# IOandSensors.net
KiCad netlist of a schematic drawn in Altium Designer
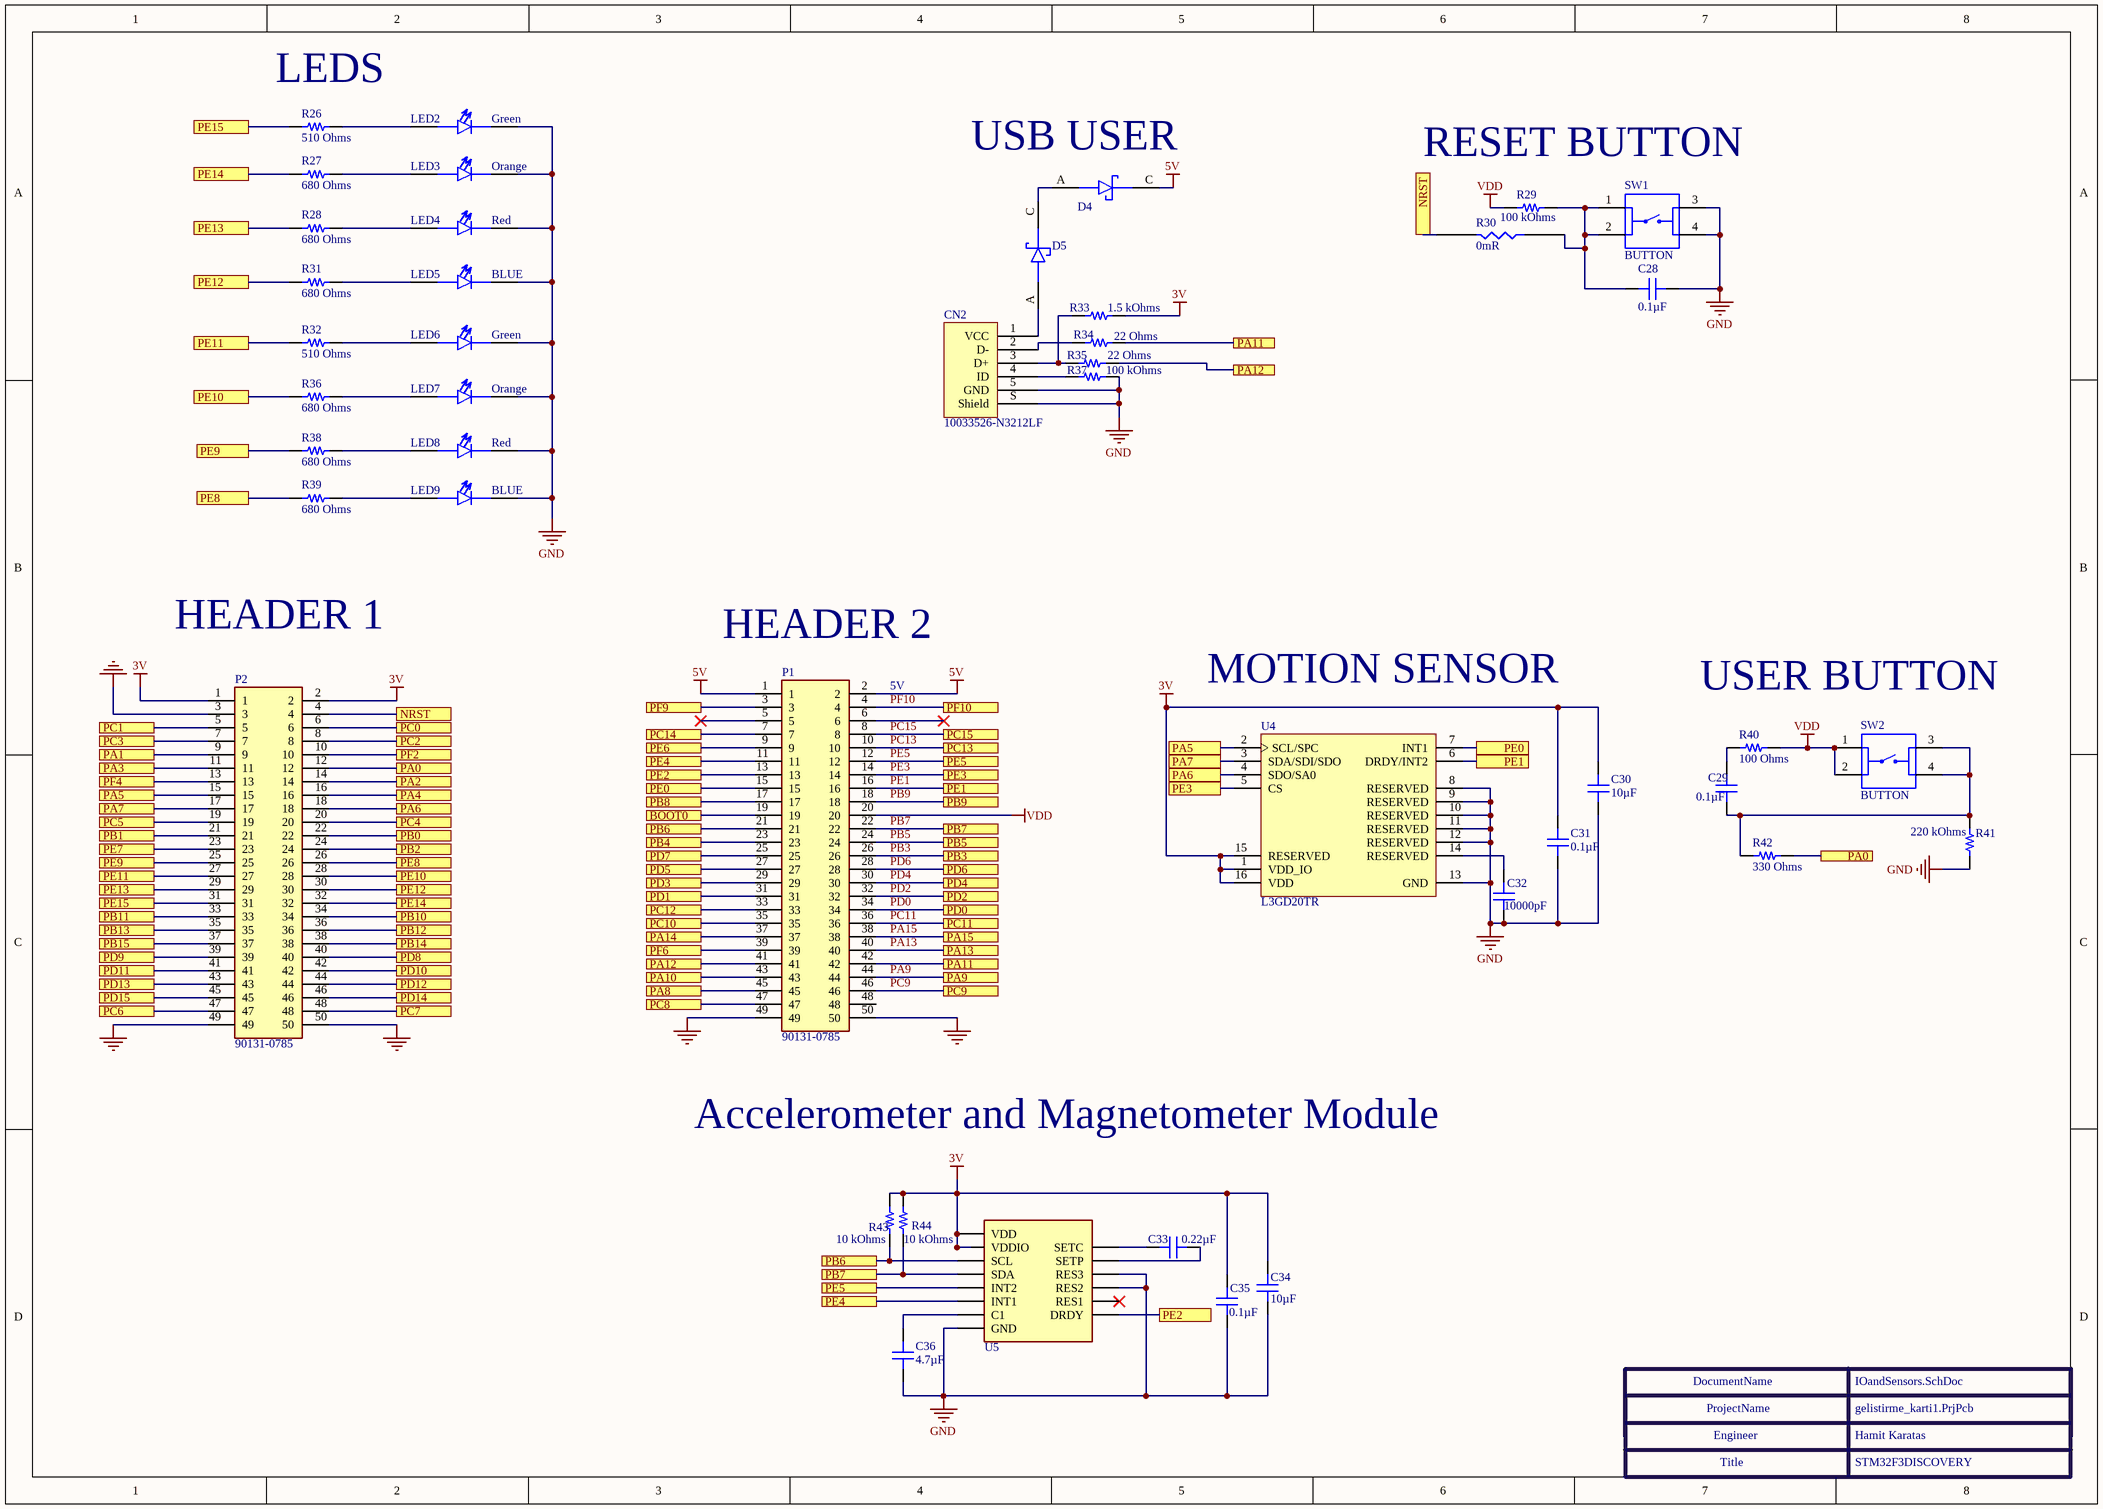
[diagram p0: IOandSensors.SchDoc]

(export (version "E")
  (design (tool "Eeschema 10.0.6"))
  (components
    (comp (ref "C28")
      (value "0.1µF")
      (footprint "CAP 0603_1608")
      (description "CAP CER 0.1UF 50V X7R 0603")
      (fields (field (name "PART NUMBER") "C0603C104K5RAC7411") (field (name "MANUFACTURER") "KEMET"))
      (libsource (lib "Celestial Altium Library - altium_library (4)") (part "Capacitor"))
    )
    (comp (ref "C29")
      (value "0.1µF")
      (footprint "CAP 0603_1608")
      (description "CAP CER 0.1UF 50V X7R 0603")
      (fields (field (name "PART NUMBER") "C0603C104K5RAC7411") (field (name "MANUFACTURER") "KEMET"))
      (libsource (lib "Celestial Altium Library - altium_library (4)") (part "Capacitor"))
    )
    (comp (ref "C30")
      (value "10µF")
      (footprint "CAP 0603_1608")
      (description "CAP CER 10UF 6.3V X5R 0603")
      (fields
        (field (name "PART NUMBER") "GRM188R60J106ME47D")
        (field (name "MANUFACTURER") "Murata Electronics")
      )
      (libsource (lib "Celestial Altium Library - altium_library (4)") (part "Capacitor"))
    )
    (comp (ref "C31")
      (value "0.1µF")
      (footprint "CAP 0603_1608")
      (description "CAP CER 0.1UF 50V X7R 0603")
      (fields (field (name "PART NUMBER") "C0603C104K5RAC7411") (field (name "MANUFACTURER") "KEMET"))
      (libsource (lib "Celestial Altium Library - altium_library (4)") (part "Capacitor"))
    )
    (comp (ref "C32")
      (value "10000pF")
      (footprint "CAP 0603_1608")
      (description "CAP CER 0603 10NF 100V X7R")
      (fields (field (name "PART NUMBER") "C0603X103K1RAC3316") (field (name "MANUFACTURER") "KEMET"))
      (libsource (lib "Celestial Altium Library - altium_library (4)") (part "Capacitor"))
    )
    (comp (ref "C33")
      (value "0.22µF")
      (footprint "CAP 0603_1608")
      (description "CAP CER 0603 220NF 16V X7R 10%")
      (fields (field (name "PART NUMBER") "C0603C224K4RECAUTO") (field (name "MANUFACTURER") "KEMET"))
      (libsource (lib "Celestial Altium Library - altium_library (4)") (part "Capacitor"))
    )
    (comp (ref "C34")
      (value "10µF")
      (footprint "CAP 0603_1608")
      (description "CAP CER 10UF 6.3V X5R 0603")
      (fields
        (field (name "PART NUMBER") "GRM188R60J106ME47D")
        (field (name "MANUFACTURER") "Murata Electronics")
      )
      (libsource (lib "Celestial Altium Library - altium_library (4)") (part "Capacitor"))
    )
    (comp (ref "C35")
      (value "0.1µF")
      (footprint "CAP 0603_1608")
      (description "CAP CER 0.1UF 50V X7R 0603")
      (fields (field (name "PART NUMBER") "C0603C104K5RAC7411") (field (name "MANUFACTURER") "KEMET"))
      (libsource (lib "Celestial Altium Library - altium_library (4)") (part "Capacitor"))
    )
    (comp (ref "C36")
      (value "4.7µF")
      (footprint "CAP 0603_1608")
      (description "CAP CER 4.7UF 6.3V X5R 0603")
      (fields (field (name "PART NUMBER") "C0603C475K9PACTU") (field (name "MANUFACTURER") "KEMET"))
      (libsource (lib "Celestial Altium Library - altium_library (4)") (part "Capacitor"))
    )
    (comp (ref "CN2")
      (value "10033526-N3212LF")
      (footprint "FCI USB 10033526-N3212LF")
      (description "CONN RCPT MINI USB B 5POS SMD RA")
      (fields (field (name "MANUFACTURER") "Amphenol ICC (FCI)"))
      (libsource (lib "Celestial Altium Library - altium_library (4)") (part "USB 2.0 Type B Micro"))
    )
    (comp (ref "D4")
      (value "BAT60J")
      (footprint "SOD-323")
      (fields
        (field (name "MANUFACTURER") "STMicroelectronics")
        (field (name "MANUFACTURER PART NUMBER") "BAT60JFILM")
      )
      (libsource (lib "giris_intlib") (part "DIODE SCHOTTKY"))
    )
    (comp (ref "D5")
      (value "BAT60J")
      (footprint "SOD-323")
      (fields
        (field (name "MANUFACTURER") "STMicroelectronics")
        (field (name "MANUFACTURER PART NUMBER") "BAT60JFILM")
      )
      (libsource (lib "giris_intlib") (part "DIODE SCHOTTKY"))
    )
    (comp (ref "LED2")
      (value "Green")
      (footprint "LED GREEN 0805")
      (description "Green 0805 130 º Min 5 mcd Typical 12 mcd Water Clear Lens SMT LED LTST-C171GKT")
      (fields
        (field (name "MANUFACTURER") "Vishay Lite-On")
        (field (name "MANUFACTURER PART NUMBER") "LTST-C171GKT")
        (field (name "DESIGNED BY") "Hamit")
      )
      (libsource (lib "giris_intlib") (part "LED GREEN 0805"))
    )
    (comp (ref "LED3")
      (value "Orange")
      (footprint "LED ORANGE 0805")
      (description "LED Uni-Color Orange 610nm 2-Pin Chip 0805(2012Metric) T/R  LO R976-PS-1")
      (fields
        (field (name "MANUFACTURER") "Osram Opto")
        (field (name "MANUFACTURER PART NUMBER") "LOR976-PS-1")
      )
      (libsource (lib "giris_intlib") (part "LED ORANGE 0805"))
    )
    (comp (ref "LED4")
      (value "Red")
      (footprint "LED RED 0805")
      (description "Single Color LED, Hyper Red, Colorless Diffused, 1.3mm LH R974-LP-1")
      (fields
        (field (name "MANUFACTURER") "Osram Opto")
        (field (name "MANUFACTURER PART NUMBER") "LH R974-LP-1")
        (field (name "DESIGNED BY") "Hamit")
      )
      (libsource (lib "giris_intlib") (part "LED RED 0805"))
    )
    (comp (ref "LED5")
      (value "BLUE")
      (footprint "LED BLUE 0805")
      (description "Standard LEDs - SMD BLUE 469nm 55mcd DIFF CMDA5CB7D1S")
      (fields
        (field (name "MANUFACTURER") "VCC CHML")
        (field (name "MANUFACTURER PART NUMBER") "CMDA5CB7D1S")
      )
      (libsource (lib "giris_intlib") (part "LED BLUE 0805"))
    )
    (comp (ref "LED6")
      (value "Green")
      (footprint "LED GREEN 0805")
      (description "Green 0805 130 º Min 5 mcd Typical 12 mcd Water Clear Lens SMT LED LTST-C171GKT")
      (fields
        (field (name "MANUFACTURER") "Vishay Lite-On")
        (field (name "MANUFACTURER PART NUMBER") "LTST-C171GKT")
        (field (name "DESIGNED BY") "Hamit")
      )
      (libsource (lib "giris_intlib") (part "LED GREEN 0805"))
    )
    (comp (ref "LED7")
      (value "Orange")
      (footprint "LED ORANGE 0805")
      (description "LED Uni-Color Orange 610nm 2-Pin Chip 0805(2012Metric) T/R  LO R976-PS-1")
      (fields
        (field (name "MANUFACTURER") "Osram Opto")
        (field (name "MANUFACTURER PART NUMBER") "LOR976-PS-1")
      )
      (libsource (lib "giris_intlib") (part "LED ORANGE 0805"))
    )
    (comp (ref "LED8")
      (value "Red")
      (footprint "LED RED 0805")
      (description "Single Color LED, Hyper Red, Colorless Diffused, 1.3mm LH R974-LP-1")
      (fields
        (field (name "MANUFACTURER") "Osram Opto")
        (field (name "MANUFACTURER PART NUMBER") "LH R974-LP-1")
        (field (name "DESIGNED BY") "Hamit")
      )
      (libsource (lib "giris_intlib") (part "LED RED 0805"))
    )
    (comp (ref "LED9")
      (value "BLUE")
      (footprint "LED BLUE 0805")
      (description "Standard LEDs - SMD BLUE 469nm 55mcd DIFF CMDA5CB7D1S")
      (fields
        (field (name "MANUFACTURER") "VCC CHML")
        (field (name "MANUFACTURER PART NUMBER") "CMDA5CB7D1S")
      )
      (libsource (lib "giris_intlib") (part "LED BLUE 0805"))
    )
    (comp (ref "P1")
      (value "90131-0785")
      (footprint "altium_giris:HDRV50W100P259X254_2X25_6350X516X595P")
      (description "Connector")
      (fields (field (name "MOUSER PART NUMBER") "538-90131-0785"))
      (libsource (lib "*") (part "90131-0785"))
    )
    (comp (ref "P2")
      (value "90131-0785")
      (footprint "altium_giris:HDRV50W100P259X254_2X25_6350X516X595P")
      (description "Connector")
      (fields (field (name "MOUSER PART NUMBER") "538-90131-0785"))
      (libsource (lib "*") (part "90131-0785"))
    )
    (comp (ref "R26")
      (value "510 Ohms")
      (footprint "RES 0603_1608")
      (description "RES SMD 510 OHM 0.5% 1/5W 0603")
      (fields
        (field (name "PART NUMBER") "ERJ-PB3D5100V")
        (field (name "MANUFACTURER") "Panasonic Electronic Components")
      )
      (libsource (lib "Celestial Altium Library - altium_library (4)") (part "Resistor"))
    )
    (comp (ref "R27")
      (value "680 Ohms")
      (footprint "RES 0603_1608")
      (description "RES 680 OHM 1% 1/8W 0603")
      (fields
        (field (name "PART NUMBER") "RK73H1JTTD6800F")
        (field (name "MANUFACTURER") "KOA Speer Electronics, Inc.")
      )
      (libsource (lib "Celestial Altium Library - altium_library (4)") (part "Resistor"))
    )
    (comp (ref "R28")
      (value "680 Ohms")
      (footprint "RES 0603_1608")
      (description "RES 680 OHM 1% 1/8W 0603")
      (fields
        (field (name "PART NUMBER") "RK73H1JTTD6800F")
        (field (name "MANUFACTURER") "KOA Speer Electronics, Inc.")
      )
      (libsource (lib "Celestial Altium Library - altium_library (4)") (part "Resistor"))
    )
    (comp (ref "R29")
      (value "100 kOhms")
      (footprint "RES 0603_1608")
      (description "RES SMD 100K OHM 0.5% 1/10W 0603")
      (fields (field (name "PART NUMBER") "AT0603DRD07100KL") (field (name "MANUFACTURER") "Yageo"))
      (libsource (lib "Celestial Altium Library - altium_library (4)") (part "Resistor"))
    )
    (comp (ref "R30")
      (value "RC0603JR-070RL")
      (footprint "RES_0603")
      (description "RES SMD 0 OHM JUMPER 1/10W 0603")
      (fields
        (field (name "MANUFACTURER") "Yageo")
        (field (name "TOLERANCE") "1%")
        (field (name "RESISTANCE") "0mR")
        (field (name "DESIGNED BY") "Hamit")
      )
      (libsource (lib "giris_intlib") (part "Res 0 ohm 0603"))
    )
    (comp (ref "R31")
      (value "680 Ohms")
      (footprint "RES 0603_1608")
      (description "RES 680 OHM 1% 1/8W 0603")
      (fields
        (field (name "PART NUMBER") "RK73H1JTTD6800F")
        (field (name "MANUFACTURER") "KOA Speer Electronics, Inc.")
      )
      (libsource (lib "Celestial Altium Library - altium_library (4)") (part "Resistor"))
    )
    (comp (ref "R32")
      (value "510 Ohms")
      (footprint "RES 0603_1608")
      (description "RES SMD 510 OHM 0.5% 1/5W 0603")
      (fields
        (field (name "PART NUMBER") "ERJ-PB3D5100V")
        (field (name "MANUFACTURER") "Panasonic Electronic Components")
      )
      (libsource (lib "Celestial Altium Library - altium_library (4)") (part "Resistor"))
    )
    (comp (ref "R33")
      (value "1.5 kOhms")
      (footprint "RES 0603_1608")
      (description "RES SMD 1.5K OHM 0.1% 1/10W 0603")
      (fields
        (field (name "PART NUMBER") "ERA-3AEB152V")
        (field (name "MANUFACTURER") "Panasonic Electronic Components")
      )
      (libsource (lib "Celestial Altium Library - altium_library (4)") (part "Resistor"))
    )
    (comp (ref "R34")
      (value "22 Ohms")
      (footprint "RES 0603_1608")
      (description "RES 22 OHM 5% 1/8W 0603")
      (fields
        (field (name "PART NUMBER") "RK73B1JTTD220J")
        (field (name "MANUFACTURER") "KOA Speer Electronics, Inc.")
      )
      (libsource (lib "Celestial Altium Library - altium_library (4)") (part "Resistor"))
    )
    (comp (ref "R35")
      (value "22 Ohms")
      (footprint "RES 0603_1608")
      (description "RES 22 OHM 5% 1/8W 0603")
      (fields
        (field (name "PART NUMBER") "RK73B1JTTD220J")
        (field (name "MANUFACTURER") "KOA Speer Electronics, Inc.")
      )
      (libsource (lib "Celestial Altium Library - altium_library (4)") (part "Resistor"))
    )
    (comp (ref "R36")
      (value "680 Ohms")
      (footprint "RES 0603_1608")
      (description "RES 680 OHM 1% 1/8W 0603")
      (fields
        (field (name "PART NUMBER") "RK73H1JTTD6800F")
        (field (name "MANUFACTURER") "KOA Speer Electronics, Inc.")
      )
      (libsource (lib "Celestial Altium Library - altium_library (4)") (part "Resistor"))
    )
    (comp (ref "R37")
      (value "100 kOhms")
      (footprint "RES 0603_1608")
      (description "RES SMD 100K OHM 0.5% 1/10W 0603")
      (fields (field (name "PART NUMBER") "AT0603DRD07100KL") (field (name "MANUFACTURER") "Yageo"))
      (libsource (lib "Celestial Altium Library - altium_library (4)") (part "Resistor"))
    )
    (comp (ref "R38")
      (value "680 Ohms")
      (footprint "RES 0603_1608")
      (description "RES 680 OHM 1% 1/8W 0603")
      (fields
        (field (name "PART NUMBER") "RK73H1JTTD6800F")
        (field (name "MANUFACTURER") "KOA Speer Electronics, Inc.")
      )
      (libsource (lib "Celestial Altium Library - altium_library (4)") (part "Resistor"))
    )
    (comp (ref "R39")
      (value "680 Ohms")
      (footprint "RES 0603_1608")
      (description "RES 680 OHM 1% 1/8W 0603")
      (fields
        (field (name "PART NUMBER") "RK73H1JTTD6800F")
        (field (name "MANUFACTURER") "KOA Speer Electronics, Inc.")
      )
      (libsource (lib "Celestial Altium Library - altium_library (4)") (part "Resistor"))
    )
    (comp (ref "R40")
      (value "100 Ohms")
      (footprint "RES 0603_1608")
      (description "RES 100 OHM 0.1% 1/16W 0603")
      (fields
        (field (name "PART NUMBER") "RNCS0603BKE100R")
        (field (name "MANUFACTURER") "Stackpole Electronics Inc")
      )
      (libsource (lib "Celestial Altium Library - altium_library (4)") (part "Resistor"))
    )
    (comp (ref "R41")
      (value "220 kOhms")
      (footprint "RES 0603_1608")
      (description "RES SMD 220K OHM 5% 1/10W 0603")
      (fields (field (name "PART NUMBER") "AC0603JR-07220KL") (field (name "MANUFACTURER") "Yageo"))
      (libsource (lib "Celestial Altium Library - altium_library (4)") (part "Resistor"))
    )
    (comp (ref "R42")
      (value "330 Ohms")
      (footprint "RES 0603_1608")
      (description "RES SMD 330 OHM 1% 1/10W 0603")
      (fields (field (name "PART NUMBER") "AF0603FR-07330RL") (field (name "MANUFACTURER") "Yageo"))
      (libsource (lib "Celestial Altium Library - altium_library (4)") (part "Resistor"))
    )
    (comp (ref "R43")
      (value "10 kOhms")
      (footprint "RES 0603_1608")
      (description "RES SMD 10K OHM 0.5% 1/10W 0603")
      (fields (field (name "PART NUMBER") "RT0603DRD0710KL") (field (name "MANUFACTURER") "Yageo"))
      (libsource (lib "Celestial Altium Library - altium_library (4)") (part "Resistor"))
    )
    (comp (ref "R44")
      (value "10 kOhms")
      (footprint "RES 0603_1608")
      (description "RES SMD 10K OHM 0.5% 1/10W 0603")
      (fields (field (name "PART NUMBER") "RT0603DRD0710KL") (field (name "MANUFACTURER") "Yageo"))
      (libsource (lib "Celestial Altium Library - altium_library (4)") (part "Resistor"))
    )
    (comp (ref "SW1")
      (value "BUTTON")
      (footprint "BUTTON")
      (description "6X6, H5,  160G TAC.SWITCH, 1825910-6")
      (fields
        (field (name "MANUFACTURER") "TE Connectivity Alcoswitch")
        (field (name "MANUFACTURER PART NUMBER") "1825910-6")
      )
      (libsource (lib "giris_intlib") (part "BUTTON"))
    )
    (comp (ref "SW2")
      (value "BUTTON")
      (footprint "BUTTON")
      (description "6X6, H5,  160G TAC.SWITCH, 1825910-6")
      (fields
        (field (name "MANUFACTURER") "TE Connectivity Alcoswitch")
        (field (name "MANUFACTURER PART NUMBER") "1825910-6")
      )
      (libsource (lib "giris_intlib") (part "BUTTON"))
    )
    (comp (ref "U4")
      (value "L3GD20TR")
      (footprint "LGA-16")
      (description "MOTION MEMS CONSUMER")
      (fields (field (name "MANUFACTURER") "STMicroelectronics"))
      (libsource (lib "giris_intlib") (part "Sensor_Gyroscope"))
    )
    (comp (ref "U5")
      (value "LSM303DLHCTR")
      (footprint "VFLGA-14")
      (description "IMU ACCEL/MAG 3-AXIS I2C 14LGA")
      (fields (field (name "MANUFACTURER") "STMicroelectronics"))
      (libsource (lib "giris_intlib") (part "Sensor_accelerometer_magnetometer"))
    )
  )
  (nets
    (net (code "1") (name "/BOOT0") (class "Default")
      (node (ref "P1") (pin "19") (pinfunction "19_19") (pintype "passive"))
    )
    (net (code "2") (name "/NRST") (class "Default")
      (node (ref "P2") (pin "4") (pinfunction "4_4") (pintype "passive"))
      (node (ref "R30") (pin "2") (pinfunction "2_2") (pintype "passive"))
    )
    (net (code "3") (name "/PA0") (class "Default")
      (node (ref "P2") (pin "12") (pinfunction "12_12") (pintype "passive"))
      (node (ref "R42") (pin "1") (pinfunction "1_1") (pintype "passive"))
    )
    (net (code "4") (name "/PA1") (class "Default")
      (node (ref "P2") (pin "9") (pinfunction "9_9") (pintype "passive"))
    )
    (net (code "5") (name "/PA2") (class "Default")
      (node (ref "P2") (pin "14") (pinfunction "14_14") (pintype "passive"))
    )
    (net (code "6") (name "/PA3") (class "Default")
      (node (ref "P2") (pin "11") (pinfunction "11_11") (pintype "passive"))
    )
    (net (code "7") (name "/PA4") (class "Default")
      (node (ref "P2") (pin "16") (pinfunction "16_16") (pintype "passive"))
    )
    (net (code "8") (name "/PA5") (class "Default")
      (node (ref "P2") (pin "15") (pinfunction "15_15") (pintype "passive"))
      (node (ref "U4") (pin "2") (pinfunction "SCL/SPC_2") (pintype "passive"))
    )
    (net (code "9") (name "/PA6") (class "Default")
      (node (ref "P2") (pin "18") (pinfunction "18_18") (pintype "passive"))
      (node (ref "U4") (pin "4") (pinfunction "SDO/SA0_4") (pintype "passive"))
    )
    (net (code "10") (name "/PA7") (class "Default")
      (node (ref "P2") (pin "17") (pinfunction "17_17") (pintype "passive"))
      (node (ref "U4") (pin "3") (pinfunction "SDA/SDI/SDO_3") (pintype "passive"))
    )
    (net (code "11") (name "/PA8") (class "Default")
      (node (ref "P1") (pin "45") (pinfunction "45_45") (pintype "passive"))
    )
    (net (code "12") (name "/PA9") (class "Default")
      (node (ref "P1") (pin "44") (pinfunction "44_44") (pintype "passive"))
    )
    (net (code "13") (name "/PA10") (class "Default")
      (node (ref "P1") (pin "43") (pinfunction "43_43") (pintype "passive"))
    )
    (net (code "14") (name "/PA11") (class "Default")
      (node (ref "P1") (pin "42") (pinfunction "42_42") (pintype "passive"))
      (node (ref "R34") (pin "2") (pinfunction "2_2") (pintype "passive"))
    )
    (net (code "15") (name "/PA12") (class "Default")
      (node (ref "P1") (pin "41") (pinfunction "41_41") (pintype "passive"))
      (node (ref "R35") (pin "2") (pinfunction "2_2") (pintype "passive"))
    )
    (net (code "16") (name "/PA13") (class "Default")
      (node (ref "P1") (pin "40") (pinfunction "40_40") (pintype "passive"))
    )
    (net (code "17") (name "/PA14") (class "Default")
      (node (ref "P1") (pin "37") (pinfunction "37_37") (pintype "passive"))
    )
    (net (code "18") (name "/PA15") (class "Default")
      (node (ref "P1") (pin "38") (pinfunction "38_38") (pintype "passive"))
    )
    (net (code "19") (name "/PB0") (class "Default")
      (node (ref "P2") (pin "22") (pinfunction "22_22") (pintype "passive"))
    )
    (net (code "20") (name "/PB1") (class "Default")
      (node (ref "P2") (pin "21") (pinfunction "21_21") (pintype "passive"))
    )
    (net (code "21") (name "/PB2") (class "Default")
      (node (ref "P2") (pin "24") (pinfunction "24_24") (pintype "passive"))
    )
    (net (code "22") (name "/PB3") (class "Default")
      (node (ref "P1") (pin "26") (pinfunction "26_26") (pintype "passive"))
    )
    (net (code "23") (name "/PB4") (class "Default")
      (node (ref "P1") (pin "23") (pinfunction "23_23") (pintype "passive"))
    )
    (net (code "24") (name "/PB5") (class "Default")
      (node (ref "P1") (pin "24") (pinfunction "24_24") (pintype "passive"))
    )
    (net (code "25") (name "/PB6") (class "Default")
      (node (ref "P1") (pin "21") (pinfunction "21_21") (pintype "passive"))
      (node (ref "R43") (pin "1") (pinfunction "1_1") (pintype "passive"))
      (node (ref "U5") (pin "P$2") (pinfunction "SCL_P$2") (pintype "passive"))
    )
    (net (code "26") (name "/PB7") (class "Default")
      (node (ref "P1") (pin "22") (pinfunction "22_22") (pintype "passive"))
      (node (ref "R44") (pin "1") (pinfunction "1_1") (pintype "passive"))
      (node (ref "U5") (pin "P$3") (pinfunction "SDA_P$3") (pintype "passive"))
    )
    (net (code "27") (name "/PB8") (class "Default")
      (node (ref "P1") (pin "17") (pinfunction "17_17") (pintype "passive"))
    )
    (net (code "28") (name "/PB9") (class "Default")
      (node (ref "P1") (pin "18") (pinfunction "18_18") (pintype "passive"))
    )
    (net (code "29") (name "/PB10") (class "Default")
      (node (ref "P2") (pin "34") (pinfunction "34_34") (pintype "passive"))
    )
    (net (code "30") (name "/PB11") (class "Default")
      (node (ref "P2") (pin "33") (pinfunction "33_33") (pintype "passive"))
    )
    (net (code "31") (name "/PB12") (class "Default")
      (node (ref "P2") (pin "36") (pinfunction "36_36") (pintype "passive"))
    )
    (net (code "32") (name "/PB13") (class "Default")
      (node (ref "P2") (pin "35") (pinfunction "35_35") (pintype "passive"))
    )
    (net (code "33") (name "/PB14") (class "Default")
      (node (ref "P2") (pin "38") (pinfunction "38_38") (pintype "passive"))
    )
    (net (code "34") (name "/PB15") (class "Default")
      (node (ref "P2") (pin "37") (pinfunction "37_37") (pintype "passive"))
    )
    (net (code "35") (name "/PC0") (class "Default")
      (node (ref "P2") (pin "6") (pinfunction "6_6") (pintype "passive"))
    )
    (net (code "36") (name "/PC1") (class "Default")
      (node (ref "P2") (pin "5") (pinfunction "5_5") (pintype "passive"))
    )
    (net (code "37") (name "/PC2") (class "Default")
      (node (ref "P2") (pin "8") (pinfunction "8_8") (pintype "passive"))
    )
    (net (code "38") (name "/PC3") (class "Default")
      (node (ref "P2") (pin "7") (pinfunction "7_7") (pintype "passive"))
    )
    (net (code "39") (name "/PC4") (class "Default")
      (node (ref "P2") (pin "20") (pinfunction "20_20") (pintype "passive"))
    )
    (net (code "40") (name "/PC5") (class "Default")
      (node (ref "P2") (pin "19") (pinfunction "19_19") (pintype "passive"))
    )
    (net (code "41") (name "/PC6") (class "Default")
      (node (ref "P2") (pin "47") (pinfunction "47_47") (pintype "passive"))
    )
    (net (code "42") (name "/PC7") (class "Default")
      (node (ref "P2") (pin "48") (pinfunction "48_48") (pintype "passive"))
    )
    (net (code "43") (name "/PC8") (class "Default")
      (node (ref "P1") (pin "47") (pinfunction "47_47") (pintype "passive"))
    )
    (net (code "44") (name "/PC9") (class "Default")
      (node (ref "P1") (pin "46") (pinfunction "46_46") (pintype "passive"))
    )
    (net (code "45") (name "/PC10") (class "Default")
      (node (ref "P1") (pin "35") (pinfunction "35_35") (pintype "passive"))
    )
    (net (code "46") (name "/PC11") (class "Default")
      (node (ref "P1") (pin "36") (pinfunction "36_36") (pintype "passive"))
    )
    (net (code "47") (name "/PC12") (class "Default")
      (node (ref "P1") (pin "33") (pinfunction "33_33") (pintype "passive"))
    )
    (net (code "48") (name "/PC13") (class "Default")
      (node (ref "P1") (pin "10") (pinfunction "10_10") (pintype "passive"))
    )
    (net (code "49") (name "/PC14") (class "Default")
      (node (ref "P1") (pin "7") (pinfunction "7_7") (pintype "passive"))
    )
    (net (code "50") (name "/PC15") (class "Default")
      (node (ref "P1") (pin "8") (pinfunction "8_8") (pintype "passive"))
    )
    (net (code "51") (name "/PD0") (class "Default")
      (node (ref "P1") (pin "34") (pinfunction "34_34") (pintype "passive"))
    )
    (net (code "52") (name "/PD1") (class "Default")
      (node (ref "P1") (pin "31") (pinfunction "31_31") (pintype "passive"))
    )
    (net (code "53") (name "/PD2") (class "Default")
      (node (ref "P1") (pin "32") (pinfunction "32_32") (pintype "passive"))
    )
    (net (code "54") (name "/PD3") (class "Default")
      (node (ref "P1") (pin "29") (pinfunction "29_29") (pintype "passive"))
    )
    (net (code "55") (name "/PD4") (class "Default")
      (node (ref "P1") (pin "30") (pinfunction "30_30") (pintype "passive"))
    )
    (net (code "56") (name "/PD5") (class "Default")
      (node (ref "P1") (pin "27") (pinfunction "27_27") (pintype "passive"))
    )
    (net (code "57") (name "/PD6") (class "Default")
      (node (ref "P1") (pin "28") (pinfunction "28_28") (pintype "passive"))
    )
    (net (code "58") (name "/PD7") (class "Default")
      (node (ref "P1") (pin "25") (pinfunction "25_25") (pintype "passive"))
    )
    (net (code "59") (name "/PD8") (class "Default")
      (node (ref "P2") (pin "40") (pinfunction "40_40") (pintype "passive"))
    )
    (net (code "60") (name "/PD9") (class "Default")
      (node (ref "P2") (pin "39") (pinfunction "39_39") (pintype "passive"))
    )
    (net (code "61") (name "/PD10") (class "Default")
      (node (ref "P2") (pin "42") (pinfunction "42_42") (pintype "passive"))
    )
    (net (code "62") (name "/PD11") (class "Default")
      (node (ref "P2") (pin "41") (pinfunction "41_41") (pintype "passive"))
    )
    (net (code "63") (name "/PD12") (class "Default")
      (node (ref "P2") (pin "44") (pinfunction "44_44") (pintype "passive"))
    )
    (net (code "64") (name "/PD13") (class "Default")
      (node (ref "P2") (pin "43") (pinfunction "43_43") (pintype "passive"))
    )
    (net (code "65") (name "/PD14") (class "Default")
      (node (ref "P2") (pin "46") (pinfunction "46_46") (pintype "passive"))
    )
    (net (code "66") (name "/PD15") (class "Default")
      (node (ref "P2") (pin "45") (pinfunction "45_45") (pintype "passive"))
    )
    (net (code "67") (name "/PE0") (class "Default")
      (node (ref "P1") (pin "15") (pinfunction "15_15") (pintype "passive"))
      (node (ref "U4") (pin "7") (pinfunction "INT1_7") (pintype "passive"))
    )
    (net (code "68") (name "/PE1") (class "Default")
      (node (ref "P1") (pin "16") (pinfunction "16_16") (pintype "passive"))
      (node (ref "U4") (pin "6") (pinfunction "DRDY/INT2_6") (pintype "passive"))
    )
    (net (code "69") (name "/PE2") (class "Default")
      (node (ref "P1") (pin "13") (pinfunction "13_13") (pintype "passive"))
      (node (ref "U5") (pin "P$9") (pinfunction "DRDY_P$9") (pintype "passive"))
    )
    (net (code "70") (name "/PE3") (class "Default")
      (node (ref "P1") (pin "14") (pinfunction "14_14") (pintype "passive"))
      (node (ref "U4") (pin "5") (pinfunction "CS_5") (pintype "passive"))
    )
    (net (code "71") (name "/PE4") (class "Default")
      (node (ref "P1") (pin "11") (pinfunction "11_11") (pintype "passive"))
      (node (ref "U5") (pin "P$5") (pinfunction "INT1_P$5") (pintype "passive"))
    )
    (net (code "72") (name "/PE5") (class "Default")
      (node (ref "P1") (pin "12") (pinfunction "12_12") (pintype "passive"))
      (node (ref "U5") (pin "P$4") (pinfunction "INT2_P$4") (pintype "passive"))
    )
    (net (code "73") (name "/PE6") (class "Default")
      (node (ref "P1") (pin "9") (pinfunction "9_9") (pintype "passive"))
    )
    (net (code "74") (name "/PE7") (class "Default")
      (node (ref "P2") (pin "23") (pinfunction "23_23") (pintype "passive"))
    )
    (net (code "75") (name "/PE8") (class "Default")
      (node (ref "P2") (pin "26") (pinfunction "26_26") (pintype "passive"))
      (node (ref "R39") (pin "1") (pinfunction "1_1") (pintype "passive"))
    )
    (net (code "76") (name "/PE9") (class "Default")
      (node (ref "P2") (pin "25") (pinfunction "25_25") (pintype "passive"))
      (node (ref "R38") (pin "1") (pinfunction "1_1") (pintype "passive"))
    )
    (net (code "77") (name "/PE10") (class "Default")
      (node (ref "P2") (pin "28") (pinfunction "28_28") (pintype "passive"))
      (node (ref "R36") (pin "1") (pinfunction "1_1") (pintype "passive"))
    )
    (net (code "78") (name "/PE11") (class "Default")
      (node (ref "P2") (pin "27") (pinfunction "27_27") (pintype "passive"))
      (node (ref "R32") (pin "1") (pinfunction "1_1") (pintype "passive"))
    )
    (net (code "79") (name "/PE12") (class "Default")
      (node (ref "P2") (pin "30") (pinfunction "30_30") (pintype "passive"))
      (node (ref "R31") (pin "1") (pinfunction "1_1") (pintype "passive"))
    )
    (net (code "80") (name "/PE13") (class "Default")
      (node (ref "P2") (pin "29") (pinfunction "29_29") (pintype "passive"))
      (node (ref "R28") (pin "1") (pinfunction "1_1") (pintype "passive"))
    )
    (net (code "81") (name "/PE14") (class "Default")
      (node (ref "P2") (pin "32") (pinfunction "32_32") (pintype "passive"))
      (node (ref "R27") (pin "1") (pinfunction "1_1") (pintype "passive"))
    )
    (net (code "82") (name "/PE15") (class "Default")
      (node (ref "P2") (pin "31") (pinfunction "31_31") (pintype "passive"))
      (node (ref "R26") (pin "1") (pinfunction "1_1") (pintype "passive"))
    )
    (net (code "83") (name "/PF2") (class "Default")
      (node (ref "P2") (pin "10") (pinfunction "10_10") (pintype "passive"))
    )
    (net (code "84") (name "/PF4") (class "Default")
      (node (ref "P2") (pin "13") (pinfunction "13_13") (pintype "passive"))
    )
    (net (code "85") (name "/PF6") (class "Default")
      (node (ref "P1") (pin "39") (pinfunction "39_39") (pintype "passive"))
    )
    (net (code "86") (name "/PF9") (class "Default")
      (node (ref "P1") (pin "3") (pinfunction "3_3") (pintype "passive"))
    )
    (net (code "87") (name "/PF10") (class "Default")
      (node (ref "P1") (pin "4") (pinfunction "4_4") (pintype "passive"))
    )
    (net (code "88") (name "3V") (class "Default")
      (node (ref "C30") (pin "2") (pinfunction "2_2") (pintype "passive"))
      (node (ref "C31") (pin "2") (pinfunction "2_2") (pintype "passive"))
      (node (ref "C34") (pin "2") (pinfunction "2_2") (pintype "passive"))
      (node (ref "C35") (pin "2") (pinfunction "2_2") (pintype "passive"))
      (node (ref "P2") (pin "1") (pinfunction "1_1") (pintype "passive"))
      (node (ref "P2") (pin "2") (pinfunction "2_2") (pintype "passive"))
      (node (ref "R33") (pin "2") (pinfunction "2_2") (pintype "passive"))
      (node (ref "R43") (pin "2") (pinfunction "2_2") (pintype "passive"))
      (node (ref "R44") (pin "2") (pinfunction "2_2") (pintype "passive"))
      (node (ref "U4") (pin "1") (pinfunction "VDD_IO_1") (pintype "passive"))
      (node (ref "U4") (pin "15") (pinfunction "RESERVED_15") (pintype "passive"))
      (node (ref "U4") (pin "16") (pinfunction "VDD_16") (pintype "passive"))
      (node (ref "U5") (pin "P$1") (pinfunction "VDDIO_P$1") (pintype "passive"))
      (node (ref "U5") (pin "P$14") (pinfunction "VDD_P$14") (pintype "passive"))
    )
    (net (code "89") (name "5V") (class "Default")
      (node (ref "D4") (pin "C") (pinfunction "C_C") (pintype "power_in"))
      (node (ref "P1") (pin "1") (pinfunction "1_1") (pintype "passive"))
      (node (ref "P1") (pin "2") (pinfunction "2_2") (pintype "passive"))
    )
    (net (code "90") (name "GND") (class "Default")
      (node (ref "C28") (pin "1") (pinfunction "1_1") (pintype "passive"))
      (node (ref "C30") (pin "1") (pinfunction "1_1") (pintype "passive"))
      (node (ref "C31") (pin "1") (pinfunction "1_1") (pintype "passive"))
      (node (ref "C32") (pin "1") (pinfunction "1_1") (pintype "passive"))
      (node (ref "C34") (pin "1") (pinfunction "1_1") (pintype "passive"))
      (node (ref "C35") (pin "1") (pinfunction "1_1") (pintype "passive"))
      (node (ref "C36") (pin "1") (pinfunction "1_1") (pintype "passive"))
      (node (ref "CN2") (pin "5") (pinfunction "GND_5") (pintype "passive"))
      (node (ref "CN2") (pin "S") (pinfunction "Shield_S") (pintype "passive"))
      (node (ref "LED2") (pin "C") (pinfunction "C_C") (pintype "passive"))
      (node (ref "LED3") (pin "C") (pinfunction "C_C") (pintype "passive"))
      (node (ref "LED4") (pin "C") (pinfunction "C_C") (pintype "passive"))
      (node (ref "LED5") (pin "C") (pinfunction "C_C") (pintype "passive"))
      (node (ref "LED6") (pin "C") (pinfunction "C_C") (pintype "passive"))
      (node (ref "LED7") (pin "C") (pinfunction "C_C") (pintype "passive"))
      (node (ref "LED8") (pin "C") (pinfunction "C_C") (pintype "passive"))
      (node (ref "LED9") (pin "C") (pinfunction "C_C") (pintype "passive"))
      (node (ref "P1") (pin "49") (pinfunction "49_49") (pintype "passive"))
      (node (ref "P1") (pin "50") (pinfunction "50_50") (pintype "passive"))
      (node (ref "P2") (pin "3") (pinfunction "3_3") (pintype "passive"))
      (node (ref "P2") (pin "49") (pinfunction "49_49") (pintype "passive"))
      (node (ref "P2") (pin "50") (pinfunction "50_50") (pintype "passive"))
      (node (ref "R37") (pin "2") (pinfunction "2_2") (pintype "passive"))
      (node (ref "R41") (pin "1") (pinfunction "1_1") (pintype "passive"))
      (node (ref "SW1") (pin "3") (pinfunction "3_3") (pintype "passive"))
      (node (ref "SW1") (pin "4") (pinfunction "4_4") (pintype "passive"))
      (node (ref "U4") (pin "10") (pinfunction "RESERVED_10") (pintype "passive"))
      (node (ref "U4") (pin "11") (pinfunction "RESERVED_11") (pintype "passive"))
      (node (ref "U4") (pin "12") (pinfunction "RESERVED_12") (pintype "passive"))
      (node (ref "U4") (pin "13") (pinfunction "GND_13") (pintype "passive"))
      (node (ref "U4") (pin "8") (pinfunction "RESERVED_8") (pintype "passive"))
      (node (ref "U4") (pin "9") (pinfunction "RESERVED_9") (pintype "passive"))
      (node (ref "U5") (pin "P$10") (pinfunction "RES2_P$10") (pintype "passive"))
      (node (ref "U5") (pin "P$11") (pinfunction "RES3_P$11") (pintype "passive"))
      (node (ref "U5") (pin "P$7") (pinfunction "GND_P$7") (pintype "passive"))
    )
    (net (code "91") (name "Net-(C28-Pad2)") (class "Default")
      (node (ref "C28") (pin "2") (pinfunction "2_2") (pintype "passive"))
      (node (ref "R29") (pin "1") (pinfunction "1_1") (pintype "passive"))
      (node (ref "R30") (pin "1") (pinfunction "1_1") (pintype "passive"))
      (node (ref "SW1") (pin "1") (pinfunction "1_1") (pintype "passive"))
      (node (ref "SW1") (pin "2") (pinfunction "2_2") (pintype "passive"))
    )
    (net (code "92") (name "Net-(C29-Pad1)") (class "Default")
      (node (ref "C29") (pin "1") (pinfunction "1_1") (pintype "passive"))
      (node (ref "R41") (pin "2") (pinfunction "2_2") (pintype "passive"))
      (node (ref "R42") (pin "2") (pinfunction "2_2") (pintype "passive"))
      (node (ref "SW2") (pin "3") (pinfunction "3_3") (pintype "passive"))
      (node (ref "SW2") (pin "4") (pinfunction "4_4") (pintype "passive"))
    )
    (net (code "93") (name "Net-(C29-Pad2)") (class "Default")
      (node (ref "C29") (pin "2") (pinfunction "2_2") (pintype "passive"))
      (node (ref "R40") (pin "1") (pinfunction "1_1") (pintype "passive"))
    )
    (net (code "94") (name "Net-(C32-Pad2)") (class "Default")
      (node (ref "C32") (pin "2") (pinfunction "2_2") (pintype "passive"))
      (node (ref "U4") (pin "14") (pinfunction "RESERVED_14") (pintype "passive"))
    )
    (net (code "95") (name "Net-(CN2-D+)") (class "Default")
      (node (ref "CN2") (pin "3") (pinfunction "D+_3") (pintype "passive"))
      (node (ref "R33") (pin "1") (pinfunction "1_1") (pintype "passive"))
      (node (ref "R35") (pin "1") (pinfunction "1_1") (pintype "passive"))
    )
    (net (code "96") (name "Net-(CN2-D-)") (class "Default")
      (node (ref "CN2") (pin "2") (pinfunction "D-_2") (pintype "passive"))
      (node (ref "R34") (pin "1") (pinfunction "1_1") (pintype "passive"))
    )
    (net (code "97") (name "Net-(CN2-ID)") (class "Default")
      (node (ref "CN2") (pin "4") (pinfunction "ID_4") (pintype "passive"))
      (node (ref "R37") (pin "1") (pinfunction "1_1") (pintype "passive"))
    )
    (net (code "98") (name "Net-(CN2-VCC)") (class "Default")
      (node (ref "CN2") (pin "1") (pinfunction "VCC_1") (pintype "passive"))
      (node (ref "D5") (pin "A") (pinfunction "A_A") (pintype "passive"))
    )
    (net (code "99") (name "Net-(D4-PadA)") (class "Default")
      (node (ref "D4") (pin "A") (pinfunction "A_A") (pintype "passive"))
      (node (ref "D5") (pin "C") (pinfunction "C_C") (pintype "power_in"))
    )
    (net (code "100") (name "Net-(LED2-PadA)") (class "Default")
      (node (ref "LED2") (pin "A") (pinfunction "A_A") (pintype "passive"))
      (node (ref "R26") (pin "2") (pinfunction "2_2") (pintype "passive"))
    )
    (net (code "101") (name "Net-(LED3-PadA)") (class "Default")
      (node (ref "LED3") (pin "A") (pinfunction "A_A") (pintype "passive"))
      (node (ref "R27") (pin "2") (pinfunction "2_2") (pintype "passive"))
    )
    (net (code "102") (name "Net-(LED4-PadA)") (class "Default")
      (node (ref "LED4") (pin "A") (pinfunction "A_A") (pintype "passive"))
      (node (ref "R28") (pin "2") (pinfunction "2_2") (pintype "passive"))
    )
    (net (code "103") (name "Net-(LED5-PadA)") (class "Default")
      (node (ref "LED5") (pin "A") (pinfunction "A_A") (pintype "passive"))
      (node (ref "R31") (pin "2") (pinfunction "2_2") (pintype "passive"))
    )
    (net (code "104") (name "Net-(LED6-PadA)") (class "Default")
      (node (ref "LED6") (pin "A") (pinfunction "A_A") (pintype "passive"))
      (node (ref "R32") (pin "2") (pinfunction "2_2") (pintype "passive"))
    )
    (net (code "105") (name "Net-(LED7-PadA)") (class "Default")
      (node (ref "LED7") (pin "A") (pinfunction "A_A") (pintype "passive"))
      (node (ref "R36") (pin "2") (pinfunction "2_2") (pintype "passive"))
    )
    (net (code "106") (name "Net-(LED8-PadA)") (class "Default")
      (node (ref "LED8") (pin "A") (pinfunction "A_A") (pintype "passive"))
      (node (ref "R38") (pin "2") (pinfunction "2_2") (pintype "passive"))
    )
    (net (code "107") (name "Net-(LED9-PadA)") (class "Default")
      (node (ref "LED9") (pin "A") (pinfunction "A_A") (pintype "passive"))
      (node (ref "R39") (pin "2") (pinfunction "2_2") (pintype "passive"))
    )
    (net (code "108") (name "Net-(U5-C1)") (class "Default")
      (node (ref "C36") (pin "2") (pinfunction "2_2") (pintype "passive"))
      (node (ref "U5") (pin "P$6") (pinfunction "C1_P$6") (pintype "passive"))
    )
    (net (code "109") (name "Net-(U5-SETC)") (class "Default")
      (node (ref "C33") (pin "1") (pinfunction "1_1") (pintype "passive"))
      (node (ref "U5") (pin "P$13") (pinfunction "SETC_P$13") (pintype "passive"))
    )
    (net (code "110") (name "Net-(U5-SETP)") (class "Default")
      (node (ref "C33") (pin "2") (pinfunction "2_2") (pintype "passive"))
      (node (ref "U5") (pin "P$12") (pinfunction "SETP_P$12") (pintype "passive"))
    )
    (net (code "111") (name "VDD") (class "Default")
      (node (ref "P1") (pin "20") (pinfunction "20_20") (pintype "passive"))
      (node (ref "R29") (pin "2") (pinfunction "2_2") (pintype "passive"))
      (node (ref "R40") (pin "2") (pinfunction "2_2") (pintype "passive"))
      (node (ref "SW2") (pin "1") (pinfunction "1_1") (pintype "passive"))
      (node (ref "SW2") (pin "2") (pinfunction "2_2") (pintype "passive"))
    )
    (net (code "112") (name "unconnected-(P1-Pad5)") (class "Default")
      (node (ref "P1") (pin "5") (pinfunction "5_5") (pintype "passive+no_connect"))
    )
    (net (code "113") (name "unconnected-(P1-Pad6)") (class "Default")
      (node (ref "P1") (pin "6") (pinfunction "6_6") (pintype "passive+no_connect"))
    )
    (net (code "114") (name "unconnected-(P1-Pad48)") (class "Default")
      (node (ref "P1") (pin "48") (pinfunction "48_48") (pintype "passive"))
    )
    (net (code "115") (name "unconnected-(U5-RES1-PadP$8)") (class "Default")
      (node (ref "U5") (pin "P$8") (pinfunction "RES1_P$8") (pintype "passive+no_connect"))
    )
  )
)
